# td8655lc.net
KiCad netlist of a schematic drawn in Altium Designer
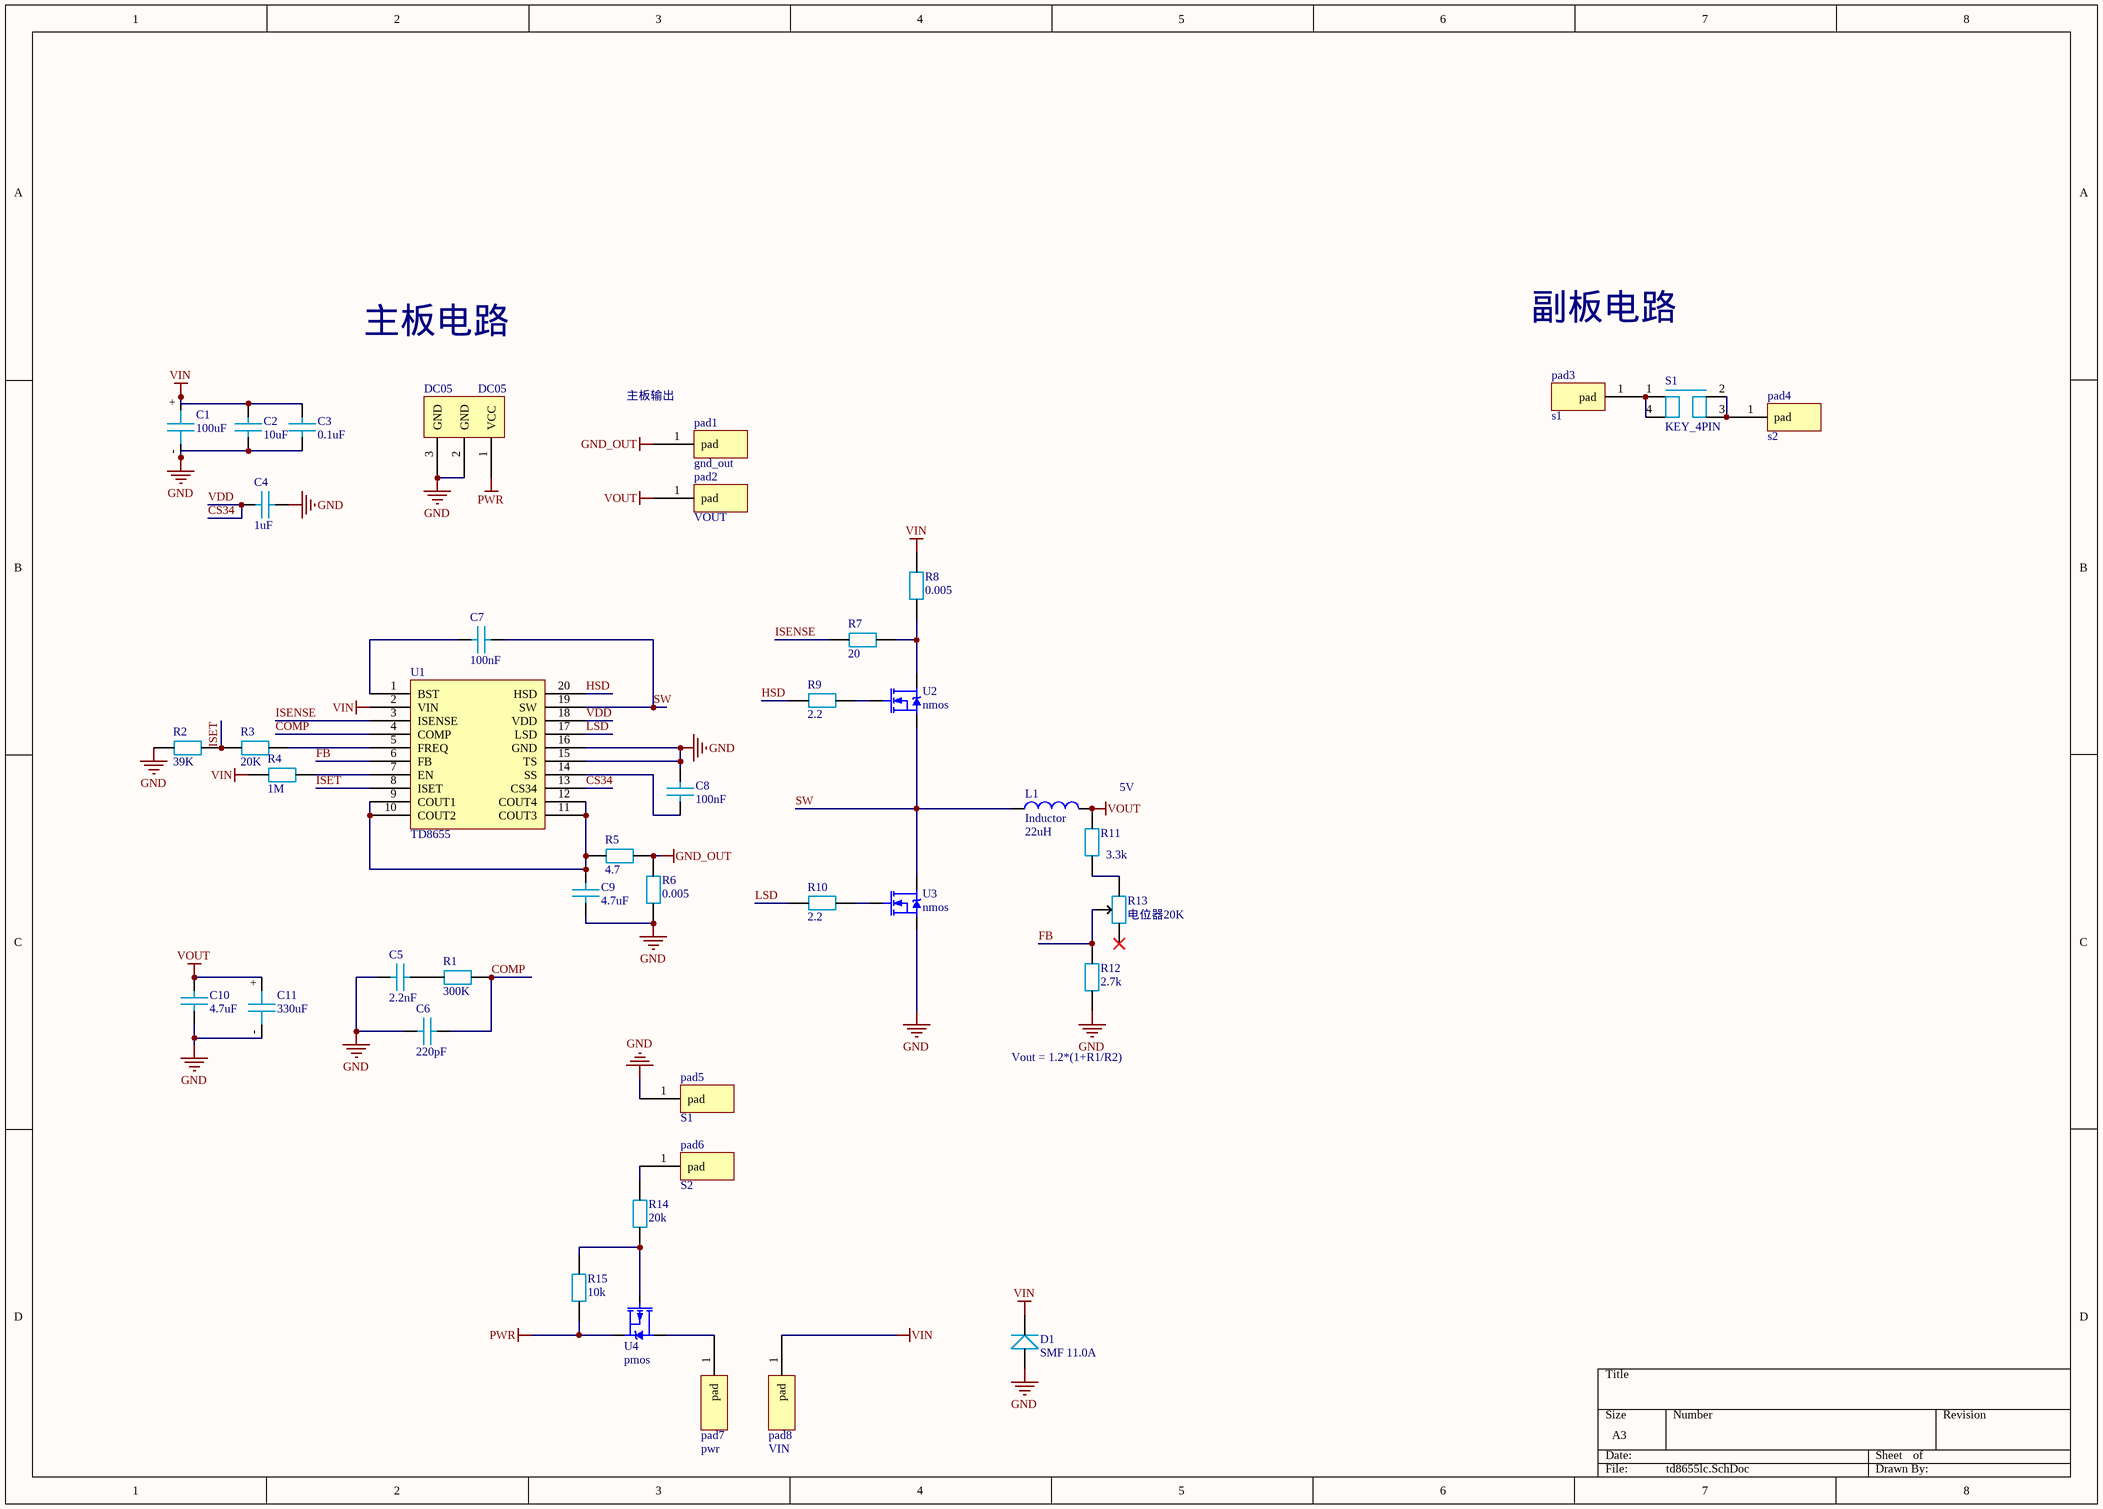
[diagram p0: td8655lc.SchDoc]

(export (version "E")
  (design (tool "Eeschema 10.0.6"))
  (components
    (comp (ref "C1")
      (value "100uF")
      (footprint "DIP-EC3.5X8X11.5-A")
      (libsource (lib "elin私人订制") (part "CD"))
    )
    (comp (ref "C2") (value "10uF") (footprint "0805_C") (libsource (lib "elin私人订制") (part "C")))
    (comp (ref "C3") (value "0.1uF") (footprint "0805_C") (libsource (lib "elin私人订制") (part "C")))
    (comp (ref "C4") (value "1uF") (footprint "0805_C") (libsource (lib "elin私人订制") (part "C")))
    (comp (ref "C5") (value "2.2nF") (footprint "0805_C") (libsource (lib "elin私人订制") (part "C")))
    (comp (ref "C6") (value "220pF") (footprint "0805_C") (libsource (lib "elin私人订制") (part "C")))
    (comp (ref "C7") (value "100nF") (footprint "0805_C") (libsource (lib "elin私人订制") (part "C")))
    (comp (ref "C8") (value "100nF") (footprint "0805_C") (libsource (lib "elin私人订制") (part "C")))
    (comp (ref "C9") (value "4.7uF") (footprint "0805_C") (libsource (lib "elin私人订制") (part "C")))
    (comp (ref "C10") (value "4.7uF") (footprint "0805_C") (libsource (lib "elin私人订制") (part "C")))
    (comp (ref "C11")
      (value "330uF")
      (footprint "DIP-EC5.0X10X16-A")
      (libsource (lib "elin私人订制") (part "CD"))
    )
    (comp (ref "D1")
      (value "SMF 11.0A")
      (footprint "LC-SOD-123F")
      (libsource (lib "elin私人订制") (part "DIODE"))
    )
    (comp (ref "DC05")
      (value "DC05")
      (footprint "dc003005互通")
      (description "DC05电源")
      (libsource (lib "elin私人订制") (part "DC05"))
    )
    (comp (ref "L1")
      (value "Inductor")
      (footprint "1040电感")
      (fields (field (name "ALTIUM_VALUE") "22uH") (field (name "PUBLISHER") "Altium Limited"))
      (libsource (lib "Miscellaneous Devices") (part "Inductor"))
    )
    (comp (ref "pad1") (value "gnd_out") (footprint "PAD 3*5") (libsource (lib "elin私人订制") (part "pad1")))
    (comp (ref "pad2") (value "VOUT") (footprint "PAD 3*5") (libsource (lib "elin私人订制") (part "pad1")))
    (comp (ref "pad3") (value "s1") (footprint "PAD贴片3*5") (libsource (lib "") (part "pad1_1")))
    (comp (ref "pad4") (value "s2") (footprint "PAD贴片3*5") (libsource (lib "elin私人订制") (part "pad1")))
    (comp (ref "pad5") (value "S1") (footprint "PAD3*3") (libsource (lib "elin私人订制") (part "pad1")))
    (comp (ref "pad6") (value "S2") (footprint "PAD3*3") (libsource (lib "elin私人订制") (part "pad1")))
    (comp (ref "pad7") (value "pwr") (footprint "PAD 3*5") (libsource (lib "") (part "pad1_2")))
    (comp (ref "pad8") (value "VIN") (footprint "PAD 3*5") (libsource (lib "") (part "pad1_2")))
    (comp (ref "R1") (value "300K") (footprint "0805_R") (libsource (lib "elin私人订制") (part "R")))
    (comp (ref "R2") (value "39K") (footprint "0805_R") (libsource (lib "elin私人订制") (part "R")))
    (comp (ref "R3") (value "20K") (footprint "0805_R") (libsource (lib "elin私人订制") (part "R")))
    (comp (ref "R4") (value "1M") (footprint "0805_R") (libsource (lib "elin私人订制") (part "R")))
    (comp (ref "R5") (value "4.7") (footprint "0805_R") (libsource (lib "elin私人订制") (part "R")))
    (comp (ref "R6") (value "0.005") (footprint "1206_R") (libsource (lib "elin私人订制") (part "R")))
    (comp (ref "R7") (value "20") (footprint "0805_R") (libsource (lib "elin私人订制") (part "R")))
    (comp (ref "R8") (value "0.005") (footprint "1206_R") (libsource (lib "elin私人订制") (part "R")))
    (comp (ref "R9") (value "2.2") (footprint "0805_R") (libsource (lib "elin私人订制") (part "R")))
    (comp (ref "R10") (value "2.2") (footprint "0805_R") (libsource (lib "elin私人订制") (part "R")))
    (comp (ref "R11") (value "3.3k") (footprint "0805_R") (libsource (lib "elin私人订制") (part "R")))
    (comp (ref "R12") (value "2.7k") (footprint "0805_R") (libsource (lib "elin私人订制") (part "R")))
    (comp (ref "R13")
      (value "电位器20K")
      (footprint "RK097N电位器")
      (libsource (lib "elin私人订制") (part "potentialmeter"))
    )
    (comp (ref "R14") (value "20k") (footprint "0805_R") (libsource (lib "elin私人订制") (part "R")))
    (comp (ref "R15") (value "10k") (footprint "0805_R") (libsource (lib "elin私人订制") (part "R")))
    (comp (ref "S1")
      (value "KEY_4PIN")
      (footprint "smd4*4轻触开关")
      (libsource (lib "elin私人订制") (part "KEY_4PIN"))
    )
    (comp (ref "U1")
      (value "TD8655")
      (footprint "LC-QFN-20_4x4x05P")
      (libsource (lib "elin私人订制") (part "TD8655"))
    )
    (comp (ref "U2") (value "nmos") (footprint "LC-DFN-8_5x6mm") (libsource (lib "elin私人订制") (part "nmos")))
    (comp (ref "U3") (value "nmos") (footprint "LC-DFN-8_5x6mm") (libsource (lib "elin私人订制") (part "nmos")))
    (comp (ref "U4") (value "pmos") (footprint "LC-DFN-8_5x6mm") (libsource (lib "elin私人订制") (part "pmos")))
  )
  (nets
    (net (code "1") (name "/COMP") (class "Default")
      (node (ref "C6") (pin "2") (pinfunction "2_2") (pintype "passive"))
      (node (ref "R1") (pin "2") (pinfunction "2_2") (pintype "passive"))
      (node (ref "U1") (pin "4") (pinfunction "COMP_4") (pintype "passive"))
    )
    (net (code "2") (name "/CS34") (class "Default")
      (node (ref "C4") (pin "2") (pinfunction "2_2") (pintype "passive"))
      (node (ref "U1") (pin "13") (pinfunction "CS34_13") (pintype "passive"))
      (node (ref "U1") (pin "18") (pinfunction "VDD_18") (pintype "passive"))
    )
    (net (code "3") (name "/FB") (class "Default")
      (node (ref "R12") (pin "2") (pinfunction "2_2") (pintype "passive"))
      (node (ref "R13") (pin "2") (pinfunction "2_2") (pintype "passive"))
      (node (ref "U1") (pin "6") (pinfunction "FB_6") (pintype "passive"))
    )
    (net (code "4") (name "/HSD") (class "Default")
      (node (ref "R9") (pin "2") (pinfunction "2_2") (pintype "passive"))
      (node (ref "U1") (pin "20") (pinfunction "HSD_20") (pintype "passive"))
    )
    (net (code "5") (name "/ISENSE") (class "Default")
      (node (ref "R7") (pin "1") (pinfunction "1_1") (pintype "passive"))
      (node (ref "U1") (pin "3") (pinfunction "ISENSE_3") (pintype "passive"))
    )
    (net (code "6") (name "/ISET") (class "Default")
      (node (ref "R2") (pin "2") (pinfunction "2_2") (pintype "passive"))
      (node (ref "R3") (pin "1") (pinfunction "1_1") (pintype "passive"))
      (node (ref "U1") (pin "8") (pinfunction "ISET_8") (pintype "passive"))
    )
    (net (code "7") (name "/LSD") (class "Default")
      (node (ref "R10") (pin "2") (pinfunction "2_2") (pintype "passive"))
      (node (ref "U1") (pin "17") (pinfunction "LSD_17") (pintype "passive"))
    )
    (net (code "8") (name "/SW") (class "Default")
      (node (ref "C7") (pin "1") (pinfunction "1_1") (pintype "passive"))
      (node (ref "L1") (pin "1") (pinfunction "1_1") (pintype "passive"))
      (node (ref "U1") (pin "19") (pinfunction "SW_19") (pintype "passive"))
      (node (ref "U2") (pin "S") (pinfunction "S_S") (pintype "passive"))
      (node (ref "U3") (pin "D") (pinfunction "D_D") (pintype "passive"))
    )
    (net (code "9") (name "GND") (class "Default")
      (node (ref "C1") (pin "-") (pinfunction "2_-") (pintype "passive"))
      (node (ref "C10") (pin "1") (pinfunction "1_1") (pintype "passive"))
      (node (ref "C11") (pin "-") (pinfunction "2_-") (pintype "passive"))
      (node (ref "C2") (pin "1") (pinfunction "1_1") (pintype "passive"))
      (node (ref "C3") (pin "1") (pinfunction "1_1") (pintype "passive"))
      (node (ref "C4") (pin "1") (pinfunction "1_1") (pintype "passive"))
      (node (ref "C5") (pin "1") (pinfunction "1_1") (pintype "passive"))
      (node (ref "C6") (pin "1") (pinfunction "1_1") (pintype "passive"))
      (node (ref "C8") (pin "2") (pinfunction "2_2") (pintype "passive"))
      (node (ref "C9") (pin "1") (pinfunction "1_1") (pintype "passive"))
      (node (ref "D1") (pin "2") (pinfunction "2_2") (pintype "passive"))
      (node (ref "DC05") (pin "2") (pinfunction "GND_2") (pintype "passive"))
      (node (ref "DC05") (pin "3") (pinfunction "GND_3") (pintype "passive"))
      (node (ref "R12") (pin "1") (pinfunction "1_1") (pintype "passive"))
      (node (ref "R2") (pin "1") (pinfunction "1_1") (pintype "passive"))
      (node (ref "R6") (pin "1") (pinfunction "1_1") (pintype "passive"))
      (node (ref "U1") (pin "15") (pinfunction "TS_15") (pintype "passive"))
      (node (ref "U1") (pin "16") (pinfunction "GND_16") (pintype "passive"))
      (node (ref "U3") (pin "S") (pinfunction "S_S") (pintype "passive"))
      (node (ref "pad5") (pin "1") (pinfunction "pad_1") (pintype "passive"))
    )
    (net (code "10") (name "GND_OUT") (class "Default")
      (node (ref "R5") (pin "2") (pinfunction "2_2") (pintype "passive"))
      (node (ref "R6") (pin "2") (pinfunction "2_2") (pintype "passive"))
      (node (ref "pad1") (pin "1") (pinfunction "pad_1") (pintype "passive"))
    )
    (net (code "11") (name "Net-(C5-Pad2)") (class "Default")
      (node (ref "C5") (pin "2") (pinfunction "2_2") (pintype "passive"))
      (node (ref "R1") (pin "1") (pinfunction "1_1") (pintype "passive"))
    )
    (net (code "12") (name "Net-(R7-Pad2)") (class "Default")
      (node (ref "R7") (pin "2") (pinfunction "2_2") (pintype "passive"))
      (node (ref "R8") (pin "1") (pinfunction "1_1") (pintype "passive"))
      (node (ref "U2") (pin "D") (pinfunction "D_D") (pintype "passive"))
    )
    (net (code "13") (name "Net-(R9-Pad1)") (class "Default")
      (node (ref "R9") (pin "1") (pinfunction "1_1") (pintype "passive"))
      (node (ref "U2") (pin "G") (pinfunction "G_G") (pintype "passive"))
    )
    (net (code "14") (name "Net-(R10-Pad1)") (class "Default")
      (node (ref "R10") (pin "1") (pinfunction "1_1") (pintype "passive"))
      (node (ref "U3") (pin "G") (pinfunction "G_G") (pintype "passive"))
    )
    (net (code "15") (name "Net-(R11-Pad1)") (class "Default")
      (node (ref "R11") (pin "1") (pinfunction "1_1") (pintype "passive"))
      (node (ref "R13") (pin "3") (pinfunction "3_3") (pintype "passive"))
    )
    (net (code "16") (name "Net-(R14-Pad1)") (class "Default")
      (node (ref "R14") (pin "1") (pinfunction "1_1") (pintype "passive"))
      (node (ref "R15") (pin "2") (pinfunction "2_2") (pintype "passive"))
      (node (ref "U4") (pin "G") (pinfunction "G_G") (pintype "passive"))
    )
    (net (code "17") (name "Net-(U1-BST)") (class "Default")
      (node (ref "C7") (pin "2") (pinfunction "2_2") (pintype "passive"))
      (node (ref "U1") (pin "1") (pinfunction "BST_1") (pintype "passive"))
    )
    (net (code "18") (name "Net-(U1-COUT1)") (class "Default")
      (node (ref "C9") (pin "2") (pinfunction "2_2") (pintype "passive"))
      (node (ref "R5") (pin "1") (pinfunction "1_1") (pintype "passive"))
      (node (ref "U1") (pin "10") (pinfunction "COUT2_10") (pintype "passive"))
      (node (ref "U1") (pin "11") (pinfunction "COUT3_11") (pintype "passive"))
      (node (ref "U1") (pin "12") (pinfunction "COUT4_12") (pintype "passive"))
      (node (ref "U1") (pin "9") (pinfunction "COUT1_9") (pintype "passive"))
    )
    (net (code "19") (name "Net-(U1-EN)") (class "Default")
      (node (ref "R4") (pin "2") (pinfunction "2_2") (pintype "passive"))
      (node (ref "U1") (pin "7") (pinfunction "EN_7") (pintype "passive"))
    )
    (net (code "20") (name "Net-(U1-FREQ)") (class "Default")
      (node (ref "R3") (pin "2") (pinfunction "2_2") (pintype "passive"))
      (node (ref "U1") (pin "5") (pinfunction "FREQ_5") (pintype "passive"))
    )
    (net (code "21") (name "Net-(U1-SS)") (class "Default")
      (node (ref "C8") (pin "1") (pinfunction "1_1") (pintype "passive"))
      (node (ref "U1") (pin "14") (pinfunction "SS_14") (pintype "passive"))
    )
    (net (code "22") (name "Net-(pad3-pad)") (class "Default")
      (node (ref "S1") (pin "1") (pinfunction "1_1") (pintype "passive"))
      (node (ref "S1") (pin "4") (pinfunction "4_4") (pintype "passive"))
      (node (ref "pad3") (pin "1") (pinfunction "pad_1") (pintype "passive"))
    )
    (net (code "23") (name "Net-(pad4-pad)") (class "Default")
      (node (ref "S1") (pin "2") (pinfunction "2_2") (pintype "passive"))
      (node (ref "S1") (pin "3") (pinfunction "3_3") (pintype "passive"))
      (node (ref "pad4") (pin "1") (pinfunction "pad_1") (pintype "passive"))
    )
    (net (code "24") (name "Net-(pad6-pad)") (class "Default")
      (node (ref "R14") (pin "2") (pinfunction "2_2") (pintype "passive"))
      (node (ref "pad6") (pin "1") (pinfunction "pad_1") (pintype "passive"))
    )
    (net (code "25") (name "Net-(pad7-pad)") (class "Default")
      (node (ref "U4") (pin "D") (pinfunction "D_D") (pintype "passive"))
      (node (ref "pad7") (pin "1") (pinfunction "pad_1") (pintype "passive"))
    )
    (net (code "26") (name "PWR") (class "Default")
      (node (ref "DC05") (pin "1") (pinfunction "VCC_1") (pintype "passive"))
      (node (ref "R15") (pin "1") (pinfunction "1_1") (pintype "passive"))
      (node (ref "U4") (pin "S") (pinfunction "S_S") (pintype "passive"))
    )
    (net (code "27") (name "VIN") (class "Default")
      (node (ref "C1") (pin "+") (pinfunction "1_+") (pintype "passive"))
      (node (ref "C2") (pin "2") (pinfunction "2_2") (pintype "passive"))
      (node (ref "C3") (pin "2") (pinfunction "2_2") (pintype "passive"))
      (node (ref "D1") (pin "1") (pinfunction "1_1") (pintype "passive"))
      (node (ref "R4") (pin "1") (pinfunction "1_1") (pintype "passive"))
      (node (ref "R8") (pin "2") (pinfunction "2_2") (pintype "passive"))
      (node (ref "U1") (pin "2") (pinfunction "VIN_2") (pintype "passive"))
      (node (ref "pad8") (pin "1") (pinfunction "pad_1") (pintype "passive"))
    )
    (net (code "28") (name "VOUT") (class "Default")
      (node (ref "C10") (pin "2") (pinfunction "2_2") (pintype "passive"))
      (node (ref "C11") (pin "+") (pinfunction "1_+") (pintype "passive"))
      (node (ref "L1") (pin "2") (pinfunction "2_2") (pintype "passive"))
      (node (ref "R11") (pin "2") (pinfunction "2_2") (pintype "passive"))
      (node (ref "pad2") (pin "1") (pinfunction "pad_1") (pintype "passive"))
    )
    (net (code "29") (name "unconnected-(R13-Pad1)") (class "Default")
      (node (ref "R13") (pin "1") (pinfunction "1_1") (pintype "passive+no_connect"))
    )
  )
)
